# MCU.net
KiCad netlist of a schematic drawn in Altium Designer
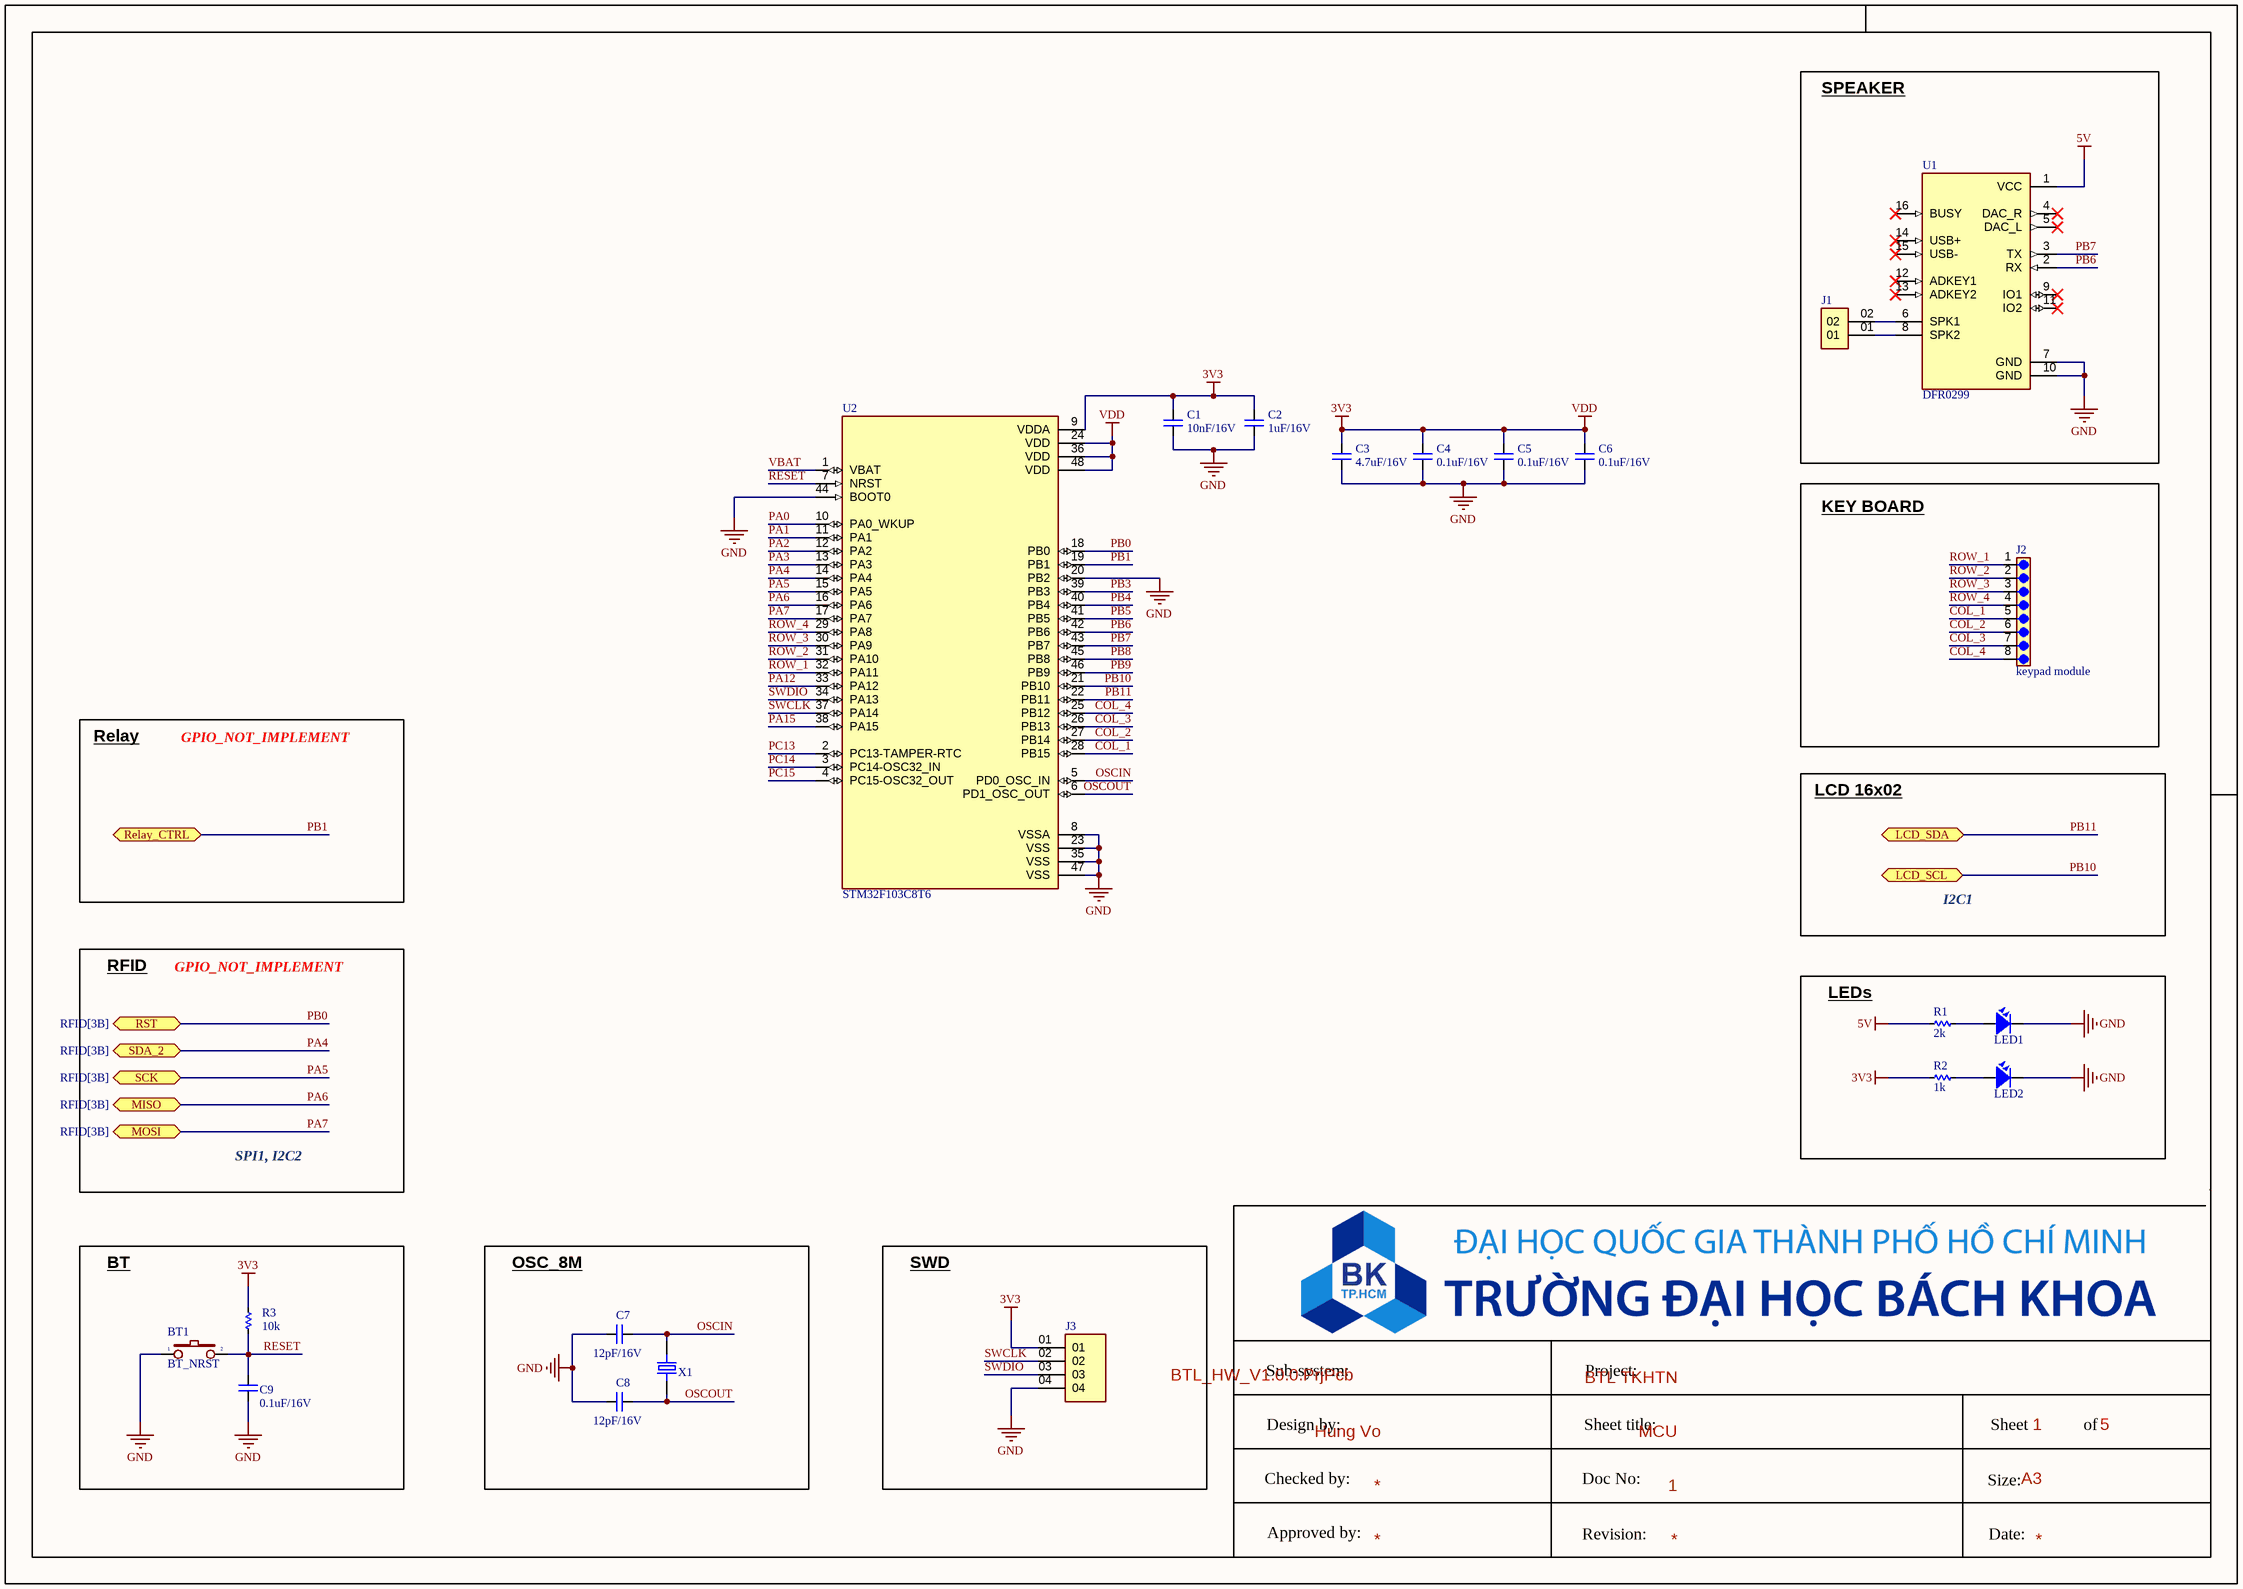
[diagram p0: MCU.SchDoc]

(export (version "E")
  (design (tool "Eeschema 10.0.6"))
  (components
    (comp (ref "BT1")
      (value "BT_NRST")
      (footprint "SW2-SMD")
      (description "Switch button 2 pin")
      (libsource (lib "C26_SCHLIB") (part "BT2"))
    )
    (comp (ref "C1")
      (value "10nF/16V")
      (footprint "CAP_C_1608X80")
      (description "CAP_Chip")
      (libsource (lib "C26_SCHLIB") (part "CAP_SMD"))
    )
    (comp (ref "C2")
      (value "1uF/16V")
      (footprint "CAP_C_1608X80")
      (description "CAP_Chip")
      (libsource (lib "C26_SCHLIB") (part "CAP_SMD"))
    )
    (comp (ref "C3")
      (value "4.7uF/16V")
      (footprint "CAP_C_1608X80")
      (description "CAP_Chip")
      (libsource (lib "C26_SCHLIB") (part "CAP_SMD"))
    )
    (comp (ref "C4")
      (value "0.1uF/16V")
      (footprint "CAP_C_1608X80")
      (description "CAP_Chip")
      (libsource (lib "C26_SCHLIB") (part "CAP_SMD"))
    )
    (comp (ref "C5")
      (value "0.1uF/16V")
      (footprint "CAP_C_1608X80")
      (description "CAP_Chip")
      (libsource (lib "C26_SCHLIB") (part "CAP_SMD"))
    )
    (comp (ref "C6")
      (value "0.1uF/16V")
      (footprint "CAP_C_1608X80")
      (description "CAP_Chip")
      (libsource (lib "C26_SCHLIB") (part "CAP_SMD"))
    )
    (comp (ref "C7")
      (value "12pF/16V")
      (footprint "CAP_C_1608X80")
      (description "CAP_Chip")
      (libsource (lib "C26_SCHLIB") (part "CAP_SMD"))
    )
    (comp (ref "C8")
      (value "12pF/16V")
      (footprint "CAP_C_1608X80")
      (description "CAP_Chip")
      (libsource (lib "C26_SCHLIB") (part "CAP_SMD"))
    )
    (comp (ref "C9")
      (value "0.1uF/16V")
      (footprint "CAP_C_1608X80")
      (description "CAP_Chip")
      (libsource (lib "C26_SCHLIB") (part "CAP_SMD"))
    )
    (comp (ref "J1")
      (value "MTSW-102-08-G-S-100-RA")
      (footprint "SAMTEC_MTSW-102-08-G-S-100-RA")
      (description "Connector Header Through Hole, Right Angle 2 position 0.100 (2.54mm)")
      (fields (field (name "MF") "Samtec"))
      (libsource (lib "BTL_SCHLIB") (part "MTSW-102-08-G-S-100-RA"))
    )
    (comp (ref "J2")
      (value "keypad module")
      (footprint "61300811121")
      (description "8 pins, 1 row, straight, gold plating")
      (fields (field (name "MF") "Wurth Electronics") (field (name "MP") "61300811121"))
      (libsource (lib "BTL_SCHLIB") (part "keypad module"))
    )
    (comp (ref "J3")
      (value "HTSW-104-08-G-S-RA")
      (footprint "SAMTEC_HTSW-104-08-G-S-RA")
      (fields (field (name "MF") "Samtec"))
      (libsource (lib "BTL_SCHLIB") (part "HTSW-104-08-G-S-RA"))
    )
    (comp (ref "LED1")
      (value "LED")
      (footprint "LED-0603-RED")
      (libsource (lib "C26_SCHLIB") (part "LED SMD"))
    )
    (comp (ref "LED2")
      (value "LED")
      (footprint "LED-0603-RED")
      (libsource (lib "C26_SCHLIB") (part "LED SMD"))
    )
    (comp (ref "R1")
      (value "2k")
      (footprint "RES_C_1608X60")
      (description "RES")
      (libsource (lib "C26_SCHLIB") (part "RES_SMD"))
    )
    (comp (ref "R2")
      (value "1k")
      (footprint "RES_C_1608X60")
      (description "RES")
      (libsource (lib "C26_SCHLIB") (part "RES_SMD"))
    )
    (comp (ref "R3")
      (value "10k")
      (footprint "RES_C_1608X60")
      (description "RES")
      (libsource (lib "C26_SCHLIB") (part "RES_SMD"))
    )
    (comp (ref "U1")
      (value "DFR0299")
      (footprint "MODULE_DFR0299")
      (description "- MP3 Player Audio Arduino Platform Evaluation Expansion Board")
      (fields (field (name "MF") "DFRobot"))
      (libsource (lib "BTL_SCHLIB") (part "DFR0299"))
    )
    (comp (ref "U2")
      (value "STM32F103C8T6")
      (footprint "QFP50P900X900X160-48N")
      (description "ARM® Cortex®-M3 STM32F1 Microcontroller IC 32-Bit 72MHz 64KB (64K x 8) FLASH 48-LQFP (7x7)")
      (fields (field (name "MF") "STMicroelectronics"))
      (libsource (lib "C26_SCHLIB") (part "STM32F103C8T6"))
    )
    (comp (ref "X1")
      (value "ECS-080-18-5PX-JES-TR")
      (footprint "XTAL 8MHz")
      (description "8 MHz Â±20ppm Crystal 18pF 60 Ohms HC-49/US")
      (fields (field (name "MF") "ECS Inc."))
      (libsource (lib "C26_SCHLIB") (part "ECS-080-18-5PX-JES-TR"))
    )
  )
  (nets
    (net (code "1") (name "/COL_1") (class "Default")
      (node (ref "J2") (pin "5") (pinfunction "5_5") (pintype "passive"))
      (node (ref "U2") (pin "28") (pinfunction "PB15_28") (pintype "bidirectional"))
    )
    (net (code "2") (name "/COL_2") (class "Default")
      (node (ref "J2") (pin "6") (pinfunction "6_6") (pintype "passive"))
      (node (ref "U2") (pin "27") (pinfunction "PB14_27") (pintype "bidirectional"))
    )
    (net (code "3") (name "/COL_3") (class "Default")
      (node (ref "J2") (pin "7") (pinfunction "7_7") (pintype "passive"))
      (node (ref "U2") (pin "26") (pinfunction "PB13_26") (pintype "bidirectional"))
    )
    (net (code "4") (name "/COL_4") (class "Default")
      (node (ref "J2") (pin "8") (pinfunction "8_8") (pintype "passive"))
      (node (ref "U2") (pin "25") (pinfunction "PB12_25") (pintype "bidirectional"))
    )
    (net (code "5") (name "/OSCIN") (class "Default")
      (node (ref "C7") (pin "2") (pinfunction "2_2") (pintype "passive"))
      (node (ref "U2") (pin "5") (pinfunction "PD0_OSC_IN_5") (pintype "bidirectional"))
      (node (ref "X1") (pin "1") (pinfunction "1_1") (pintype "passive"))
    )
    (net (code "6") (name "/OSCOUT") (class "Default")
      (node (ref "C8") (pin "2") (pinfunction "2_2") (pintype "passive"))
      (node (ref "U2") (pin "6") (pinfunction "PD1_OSC_OUT_6") (pintype "bidirectional"))
      (node (ref "X1") (pin "2") (pinfunction "2_2") (pintype "passive"))
    )
    (net (code "7") (name "/PA0") (class "Default")
      (node (ref "U2") (pin "10") (pinfunction "PA0_WKUP_10") (pintype "bidirectional"))
    )
    (net (code "8") (name "/PA1") (class "Default")
      (node (ref "U2") (pin "11") (pinfunction "PA1_11") (pintype "bidirectional"))
    )
    (net (code "9") (name "/PA2") (class "Default")
      (node (ref "U2") (pin "12") (pinfunction "PA2_12") (pintype "bidirectional"))
    )
    (net (code "10") (name "/PA3") (class "Default")
      (node (ref "U2") (pin "13") (pinfunction "PA3_13") (pintype "bidirectional"))
    )
    (net (code "11") (name "/PA4") (class "Default")
      (node (ref "U2") (pin "14") (pinfunction "PA4_14") (pintype "bidirectional"))
    )
    (net (code "12") (name "/PA5") (class "Default")
      (node (ref "U2") (pin "15") (pinfunction "PA5_15") (pintype "bidirectional"))
    )
    (net (code "13") (name "/PA6") (class "Default")
      (node (ref "U2") (pin "16") (pinfunction "PA6_16") (pintype "bidirectional"))
    )
    (net (code "14") (name "/PA7") (class "Default")
      (node (ref "U2") (pin "17") (pinfunction "PA7_17") (pintype "bidirectional"))
    )
    (net (code "15") (name "/PA12") (class "Default")
      (node (ref "U2") (pin "33") (pinfunction "PA12_33") (pintype "bidirectional"))
    )
    (net (code "16") (name "/PA15") (class "Default")
      (node (ref "U2") (pin "38") (pinfunction "PA15_38") (pintype "bidirectional"))
    )
    (net (code "17") (name "/PB0") (class "Default")
      (node (ref "U2") (pin "18") (pinfunction "PB0_18") (pintype "bidirectional"))
    )
    (net (code "18") (name "/PB1") (class "Default")
      (node (ref "U2") (pin "19") (pinfunction "PB1_19") (pintype "bidirectional"))
    )
    (net (code "19") (name "/PB3") (class "Default")
      (node (ref "U2") (pin "39") (pinfunction "PB3_39") (pintype "bidirectional"))
    )
    (net (code "20") (name "/PB4") (class "Default")
      (node (ref "U2") (pin "40") (pinfunction "PB4_40") (pintype "bidirectional"))
    )
    (net (code "21") (name "/PB5") (class "Default")
      (node (ref "U2") (pin "41") (pinfunction "PB5_41") (pintype "bidirectional"))
    )
    (net (code "22") (name "/PB6") (class "Default")
      (node (ref "U1") (pin "2") (pinfunction "RX_2") (pintype "input"))
      (node (ref "U2") (pin "42") (pinfunction "PB6_42") (pintype "bidirectional"))
    )
    (net (code "23") (name "/PB7") (class "Default")
      (node (ref "U1") (pin "3") (pinfunction "TX_3") (pintype "output"))
      (node (ref "U2") (pin "43") (pinfunction "PB7_43") (pintype "bidirectional"))
    )
    (net (code "24") (name "/PB8") (class "Default")
      (node (ref "U2") (pin "45") (pinfunction "PB8_45") (pintype "bidirectional"))
    )
    (net (code "25") (name "/PB9") (class "Default")
      (node (ref "U2") (pin "46") (pinfunction "PB9_46") (pintype "bidirectional"))
    )
    (net (code "26") (name "/PB10") (class "Default")
      (node (ref "U2") (pin "21") (pinfunction "PB10_21") (pintype "bidirectional"))
    )
    (net (code "27") (name "/PB11") (class "Default")
      (node (ref "U2") (pin "22") (pinfunction "PB11_22") (pintype "bidirectional"))
    )
    (net (code "28") (name "/PC13") (class "Default")
      (node (ref "U2") (pin "2") (pinfunction "PC13-TAMPER-RTC_2") (pintype "bidirectional"))
    )
    (net (code "29") (name "/PC14") (class "Default")
      (node (ref "U2") (pin "3") (pinfunction "PC14-OSC32_IN_3") (pintype "bidirectional"))
    )
    (net (code "30") (name "/PC15") (class "Default")
      (node (ref "U2") (pin "4") (pinfunction "PC15-OSC32_OUT_4") (pintype "bidirectional"))
    )
    (net (code "31") (name "/RESET") (class "Default")
      (node (ref "BT1") (pin "2") (pinfunction "2_2") (pintype "passive"))
      (node (ref "C9") (pin "2") (pinfunction "2_2") (pintype "passive"))
      (node (ref "R3") (pin "1") (pinfunction "1_1") (pintype "passive"))
      (node (ref "U2") (pin "7") (pinfunction "NRST_7") (pintype "input"))
    )
    (net (code "32") (name "/ROW_1") (class "Default")
      (node (ref "J2") (pin "1") (pinfunction "1_1") (pintype "passive"))
      (node (ref "U2") (pin "32") (pinfunction "PA11_32") (pintype "bidirectional"))
    )
    (net (code "33") (name "/ROW_2") (class "Default")
      (node (ref "J2") (pin "2") (pinfunction "2_2") (pintype "passive"))
      (node (ref "U2") (pin "31") (pinfunction "PA10_31") (pintype "bidirectional"))
    )
    (net (code "34") (name "/ROW_3") (class "Default")
      (node (ref "J2") (pin "3") (pinfunction "3_3") (pintype "passive"))
      (node (ref "U2") (pin "30") (pinfunction "PA9_30") (pintype "bidirectional"))
    )
    (net (code "35") (name "/ROW_4") (class "Default")
      (node (ref "J2") (pin "4") (pinfunction "4_4") (pintype "passive"))
      (node (ref "U2") (pin "29") (pinfunction "PA8_29") (pintype "bidirectional"))
    )
    (net (code "36") (name "/SWCLK") (class "Default")
      (node (ref "J3") (pin "02") (pinfunction "02_02") (pintype "passive"))
      (node (ref "U2") (pin "37") (pinfunction "PA14_37") (pintype "bidirectional"))
    )
    (net (code "37") (name "/SWDIO") (class "Default")
      (node (ref "J3") (pin "03") (pinfunction "03_03") (pintype "passive"))
      (node (ref "U2") (pin "34") (pinfunction "PA13_34") (pintype "bidirectional"))
    )
    (net (code "38") (name "/VBAT") (class "Default")
      (node (ref "U2") (pin "1") (pinfunction "VBAT_1") (pintype "bidirectional"))
    )
    (net (code "39") (name "3V3") (class "Default")
      (node (ref "C1") (pin "2") (pinfunction "2_2") (pintype "passive"))
      (node (ref "C2") (pin "2") (pinfunction "2_2") (pintype "passive"))
      (node (ref "C3") (pin "2") (pinfunction "2_2") (pintype "passive"))
      (node (ref "C4") (pin "2") (pinfunction "2_2") (pintype "passive"))
      (node (ref "C5") (pin "2") (pinfunction "2_2") (pintype "passive"))
      (node (ref "C6") (pin "2") (pinfunction "2_2") (pintype "passive"))
      (node (ref "J3") (pin "01") (pinfunction "01_01") (pintype "passive"))
      (node (ref "R2") (pin "2") (pinfunction "2_2") (pintype "passive"))
      (node (ref "R3") (pin "2") (pinfunction "2_2") (pintype "passive"))
      (node (ref "U2") (pin "24") (pinfunction "VDD_24") (pintype "power_in"))
      (node (ref "U2") (pin "36") (pinfunction "VDD_36") (pintype "power_in"))
      (node (ref "U2") (pin "48") (pinfunction "VDD_48") (pintype "power_in"))
      (node (ref "U2") (pin "9") (pinfunction "VDDA_9") (pintype "power_in"))
    )
    (net (code "40") (name "5V") (class "Default")
      (node (ref "R1") (pin "2") (pinfunction "2_2") (pintype "passive"))
      (node (ref "U1") (pin "1") (pinfunction "VCC_1") (pintype "power_in"))
    )
    (net (code "41") (name "GND") (class "Default")
      (node (ref "BT1") (pin "1") (pinfunction "1_1") (pintype "passive"))
      (node (ref "C1") (pin "1") (pinfunction "1_1") (pintype "passive"))
      (node (ref "C2") (pin "1") (pinfunction "1_1") (pintype "passive"))
      (node (ref "C3") (pin "1") (pinfunction "1_1") (pintype "passive"))
      (node (ref "C4") (pin "1") (pinfunction "1_1") (pintype "passive"))
      (node (ref "C5") (pin "1") (pinfunction "1_1") (pintype "passive"))
      (node (ref "C6") (pin "1") (pinfunction "1_1") (pintype "passive"))
      (node (ref "C7") (pin "1") (pinfunction "1_1") (pintype "passive"))
      (node (ref "C8") (pin "1") (pinfunction "1_1") (pintype "passive"))
      (node (ref "C9") (pin "1") (pinfunction "1_1") (pintype "passive"))
      (node (ref "J3") (pin "04") (pinfunction "04_04") (pintype "passive"))
      (node (ref "LED1") (pin "2") (pinfunction "2_2") (pintype "passive"))
      (node (ref "LED2") (pin "2") (pinfunction "2_2") (pintype "passive"))
      (node (ref "U1") (pin "10") (pinfunction "GND_10") (pintype "power_in"))
      (node (ref "U1") (pin "7") (pinfunction "GND_7") (pintype "power_in"))
      (node (ref "U2") (pin "20") (pinfunction "PB2_20") (pintype "bidirectional"))
      (node (ref "U2") (pin "23") (pinfunction "VSS_23") (pintype "power_in"))
      (node (ref "U2") (pin "35") (pinfunction "VSS_35") (pintype "power_in"))
      (node (ref "U2") (pin "44") (pinfunction "BOOT0_44") (pintype "input"))
      (node (ref "U2") (pin "47") (pinfunction "VSS_47") (pintype "power_in"))
      (node (ref "U2") (pin "8") (pinfunction "VSSA_8") (pintype "power_in"))
    )
    (net (code "42") (name "Net-(LED1-Pad1)") (class "Default")
      (node (ref "LED1") (pin "1") (pinfunction "1_1") (pintype "passive"))
      (node (ref "R1") (pin "1") (pinfunction "1_1") (pintype "passive"))
    )
    (net (code "43") (name "Net-(LED2-Pad1)") (class "Default")
      (node (ref "LED2") (pin "1") (pinfunction "1_1") (pintype "passive"))
      (node (ref "R2") (pin "1") (pinfunction "1_1") (pintype "passive"))
    )
    (net (code "44") (name "Net-(U1-SPK1)") (class "Default")
      (node (ref "J1") (pin "02") (pinfunction "02_02") (pintype "passive"))
      (node (ref "U1") (pin "6") (pinfunction "SPK1_6") (pintype "passive"))
    )
    (net (code "45") (name "Net-(U1-SPK2)") (class "Default")
      (node (ref "J1") (pin "01") (pinfunction "01_01") (pintype "passive"))
      (node (ref "U1") (pin "8") (pinfunction "SPK2_8") (pintype "passive"))
    )
    (net (code "46") (name "unconnected-(U1-ADKEY1-Pad12)") (class "Default")
      (node (ref "U1") (pin "12") (pinfunction "ADKEY1_12") (pintype "input+no_connect"))
    )
    (net (code "47") (name "unconnected-(U1-ADKEY2-Pad13)") (class "Default")
      (node (ref "U1") (pin "13") (pinfunction "ADKEY2_13") (pintype "input+no_connect"))
    )
    (net (code "48") (name "unconnected-(U1-BUSY-Pad16)") (class "Default")
      (node (ref "U1") (pin "16") (pinfunction "BUSY_16") (pintype "input+no_connect"))
    )
    (net (code "49") (name "unconnected-(U1-DAC_L-Pad5)") (class "Default")
      (node (ref "U1") (pin "5") (pinfunction "DAC_L_5") (pintype "output+no_connect"))
    )
    (net (code "50") (name "unconnected-(U1-DAC_R-Pad4)") (class "Default")
      (node (ref "U1") (pin "4") (pinfunction "DAC_R_4") (pintype "output+no_connect"))
    )
    (net (code "51") (name "unconnected-(U1-IO1-Pad9)") (class "Default")
      (node (ref "U1") (pin "9") (pinfunction "IO1_9") (pintype "bidirectional+no_connect"))
    )
    (net (code "52") (name "unconnected-(U1-IO2-Pad11)") (class "Default")
      (node (ref "U1") (pin "11") (pinfunction "IO2_11") (pintype "bidirectional+no_connect"))
    )
    (net (code "53") (name "unconnected-(U1-USB+-Pad14)") (class "Default")
      (node (ref "U1") (pin "14") (pinfunction "USB+_14") (pintype "input+no_connect"))
    )
    (net (code "54") (name "unconnected-(U1-USB--Pad15)") (class "Default")
      (node (ref "U1") (pin "15") (pinfunction "USB-_15") (pintype "input+no_connect"))
    )
  )
)
